# nl.net
KiCad netlist of a schematic drawn in EAGLE
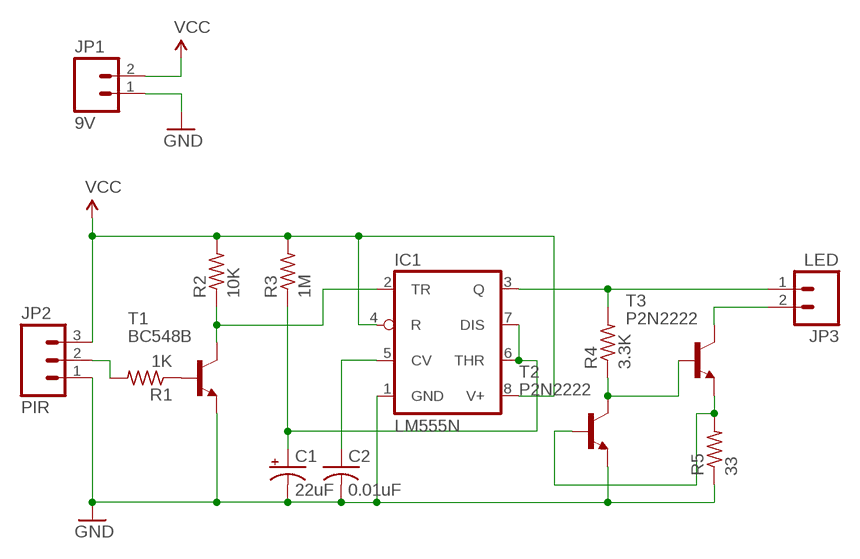
[diagram p0: schematic, sheet 1]

(export (version "E")
  (design (tool "Eeschema 10.0.6"))
  (components
    (comp (ref "C1")
      (value "22uF")
      (footprint "eagle-import:E5-6")
      (libsource (lib "eagle-import") (part "CPOL-USE5-6"))
    )
    (comp (ref "C2")
      (value "0.01uF")
      (footprint "eagle-import:C025-024X044")
      (libsource (lib "eagle-import") (part "C-US025-024X044"))
    )
    (comp (ref "IC1")
      (value "LM555N")
      (footprint "eagle-import:DIL08-ROUND")
      (libsource (lib "eagle-import") (part "555NLM"))
    )
    (comp (ref "JP1")
      (value "9V")
      (footprint "eagle-import:1X02")
      (libsource (lib "eagle-import") (part "M02PTH"))
    )
    (comp (ref "JP2")
      (value "PIR")
      (footprint "eagle-import:1X03")
      (libsource (lib "eagle-import") (part "M03PTH"))
    )
    (comp (ref "JP3")
      (value "LED")
      (footprint "eagle-import:1X02")
      (libsource (lib "eagle-import") (part "M02PTH"))
    )
    (comp (ref "R1")
      (value "1K")
      (footprint "eagle-import:0309_12")
      (libsource (lib "eagle-import") (part "R-US_0309/12"))
    )
    (comp (ref "R2")
      (value "10K")
      (footprint "eagle-import:0309_12")
      (libsource (lib "eagle-import") (part "R-US_0309/12"))
    )
    (comp (ref "R3")
      (value "1M")
      (footprint "eagle-import:0309_12")
      (libsource (lib "eagle-import") (part "R-US_0309/12"))
    )
    (comp (ref "R4")
      (value "3.3K")
      (footprint "eagle-import:0309_12")
      (libsource (lib "eagle-import") (part "R-US_0309/12"))
    )
    (comp (ref "R5")
      (value "33")
      (footprint "eagle-import:0309_12")
      (libsource (lib "eagle-import") (part "R-US_0309/12"))
    )
    (comp (ref "T1")
      (value "BC548B")
      (footprint "eagle-import:TO92-EBC")
      (libsource (lib "eagle-import") (part "BC548B"))
    )
    (comp (ref "T2")
      (value "P2N2222")
      (footprint "eagle-import:TO92-EBC")
      (libsource (lib "eagle-import") (part "BC548"))
    )
    (comp (ref "T3")
      (value "P2N2222")
      (footprint "eagle-import:TO92-EBC")
      (libsource (lib "eagle-import") (part "BC548"))
    )
  )
  (nets
    (net (code "1") (name "GND") (class "Default")
      (node (ref "C1") (pin "-") (pinfunction "-_-") (pintype "passive"))
      (node (ref "C2") (pin "2") (pinfunction "2_2") (pintype "passive"))
      (node (ref "IC1") (pin "1") (pinfunction "GND_1") (pintype "power_in"))
      (node (ref "JP1") (pin "1") (pinfunction "1_1") (pintype "passive"))
      (node (ref "JP2") (pin "1") (pinfunction "1_1") (pintype "passive"))
      (node (ref "R5") (pin "1") (pinfunction "1_1") (pintype "passive"))
      (node (ref "T1") (pin "E") (pinfunction "E_E") (pintype "passive"))
      (node (ref "T2") (pin "E") (pinfunction "E_E") (pintype "passive"))
    )
    (net (code "2") (name "Net-(IC1-CV)") (class "Default")
      (node (ref "C2") (pin "1") (pinfunction "1_1") (pintype "passive"))
      (node (ref "IC1") (pin "5") (pinfunction "CV_5") (pintype "input"))
    )
    (net (code "3") (name "Net-(IC1-DIS)") (class "Default")
      (node (ref "C1") (pin "+") (pinfunction "+_+") (pintype "passive"))
      (node (ref "IC1") (pin "6") (pinfunction "THR_6") (pintype "input"))
      (node (ref "IC1") (pin "7") (pinfunction "DIS_7") (pintype "input"))
      (node (ref "R3") (pin "1") (pinfunction "1_1") (pintype "passive"))
    )
    (net (code "4") (name "Net-(IC1-Q)") (class "Default")
      (node (ref "IC1") (pin "3") (pinfunction "Q_3") (pintype "output"))
      (node (ref "JP3") (pin "1") (pinfunction "1_1") (pintype "passive"))
      (node (ref "R4") (pin "2") (pinfunction "2_2") (pintype "passive"))
    )
    (net (code "5") (name "Net-(IC1-TR)") (class "Default")
      (node (ref "IC1") (pin "2") (pinfunction "TR_2") (pintype "input"))
      (node (ref "R2") (pin "1") (pinfunction "1_1") (pintype "passive"))
      (node (ref "T1") (pin "C") (pinfunction "C_C") (pintype "passive"))
    )
    (net (code "6") (name "Net-(JP2-Pad2)") (class "Default")
      (node (ref "JP2") (pin "2") (pinfunction "2_2") (pintype "passive"))
      (node (ref "R1") (pin "2") (pinfunction "2_2") (pintype "passive"))
    )
    (net (code "7") (name "Net-(JP3-Pad2)") (class "Default")
      (node (ref "JP3") (pin "2") (pinfunction "2_2") (pintype "passive"))
      (node (ref "T3") (pin "C") (pinfunction "C_C") (pintype "passive"))
    )
    (net (code "8") (name "Net-(R1-Pad1)") (class "Default")
      (node (ref "R1") (pin "1") (pinfunction "1_1") (pintype "passive"))
      (node (ref "T1") (pin "B") (pinfunction "B_B") (pintype "passive"))
    )
    (net (code "9") (name "Net-(R4-Pad1)") (class "Default")
      (node (ref "R4") (pin "1") (pinfunction "1_1") (pintype "passive"))
      (node (ref "T2") (pin "C") (pinfunction "C_C") (pintype "passive"))
      (node (ref "T3") (pin "B") (pinfunction "B_B") (pintype "passive"))
    )
    (net (code "10") (name "Net-(R5-Pad2)") (class "Default")
      (node (ref "R5") (pin "2") (pinfunction "2_2") (pintype "passive"))
      (node (ref "T2") (pin "B") (pinfunction "B_B") (pintype "passive"))
      (node (ref "T3") (pin "E") (pinfunction "E_E") (pintype "passive"))
    )
    (net (code "11") (name "VCC") (class "Default")
      (node (ref "IC1") (pin "4") (pinfunction "R_4") (pintype "input"))
      (node (ref "IC1") (pin "8") (pinfunction "V+_8") (pintype "power_in"))
      (node (ref "JP1") (pin "2") (pinfunction "2_2") (pintype "passive"))
      (node (ref "JP2") (pin "3") (pinfunction "3_3") (pintype "passive"))
      (node (ref "R2") (pin "2") (pinfunction "2_2") (pintype "passive"))
      (node (ref "R3") (pin "2") (pinfunction "2_2") (pintype "passive"))
    )
  )
)
